# GameboyCartridgeKS.net
KiCad netlist of a schematic drawn in EAGLE
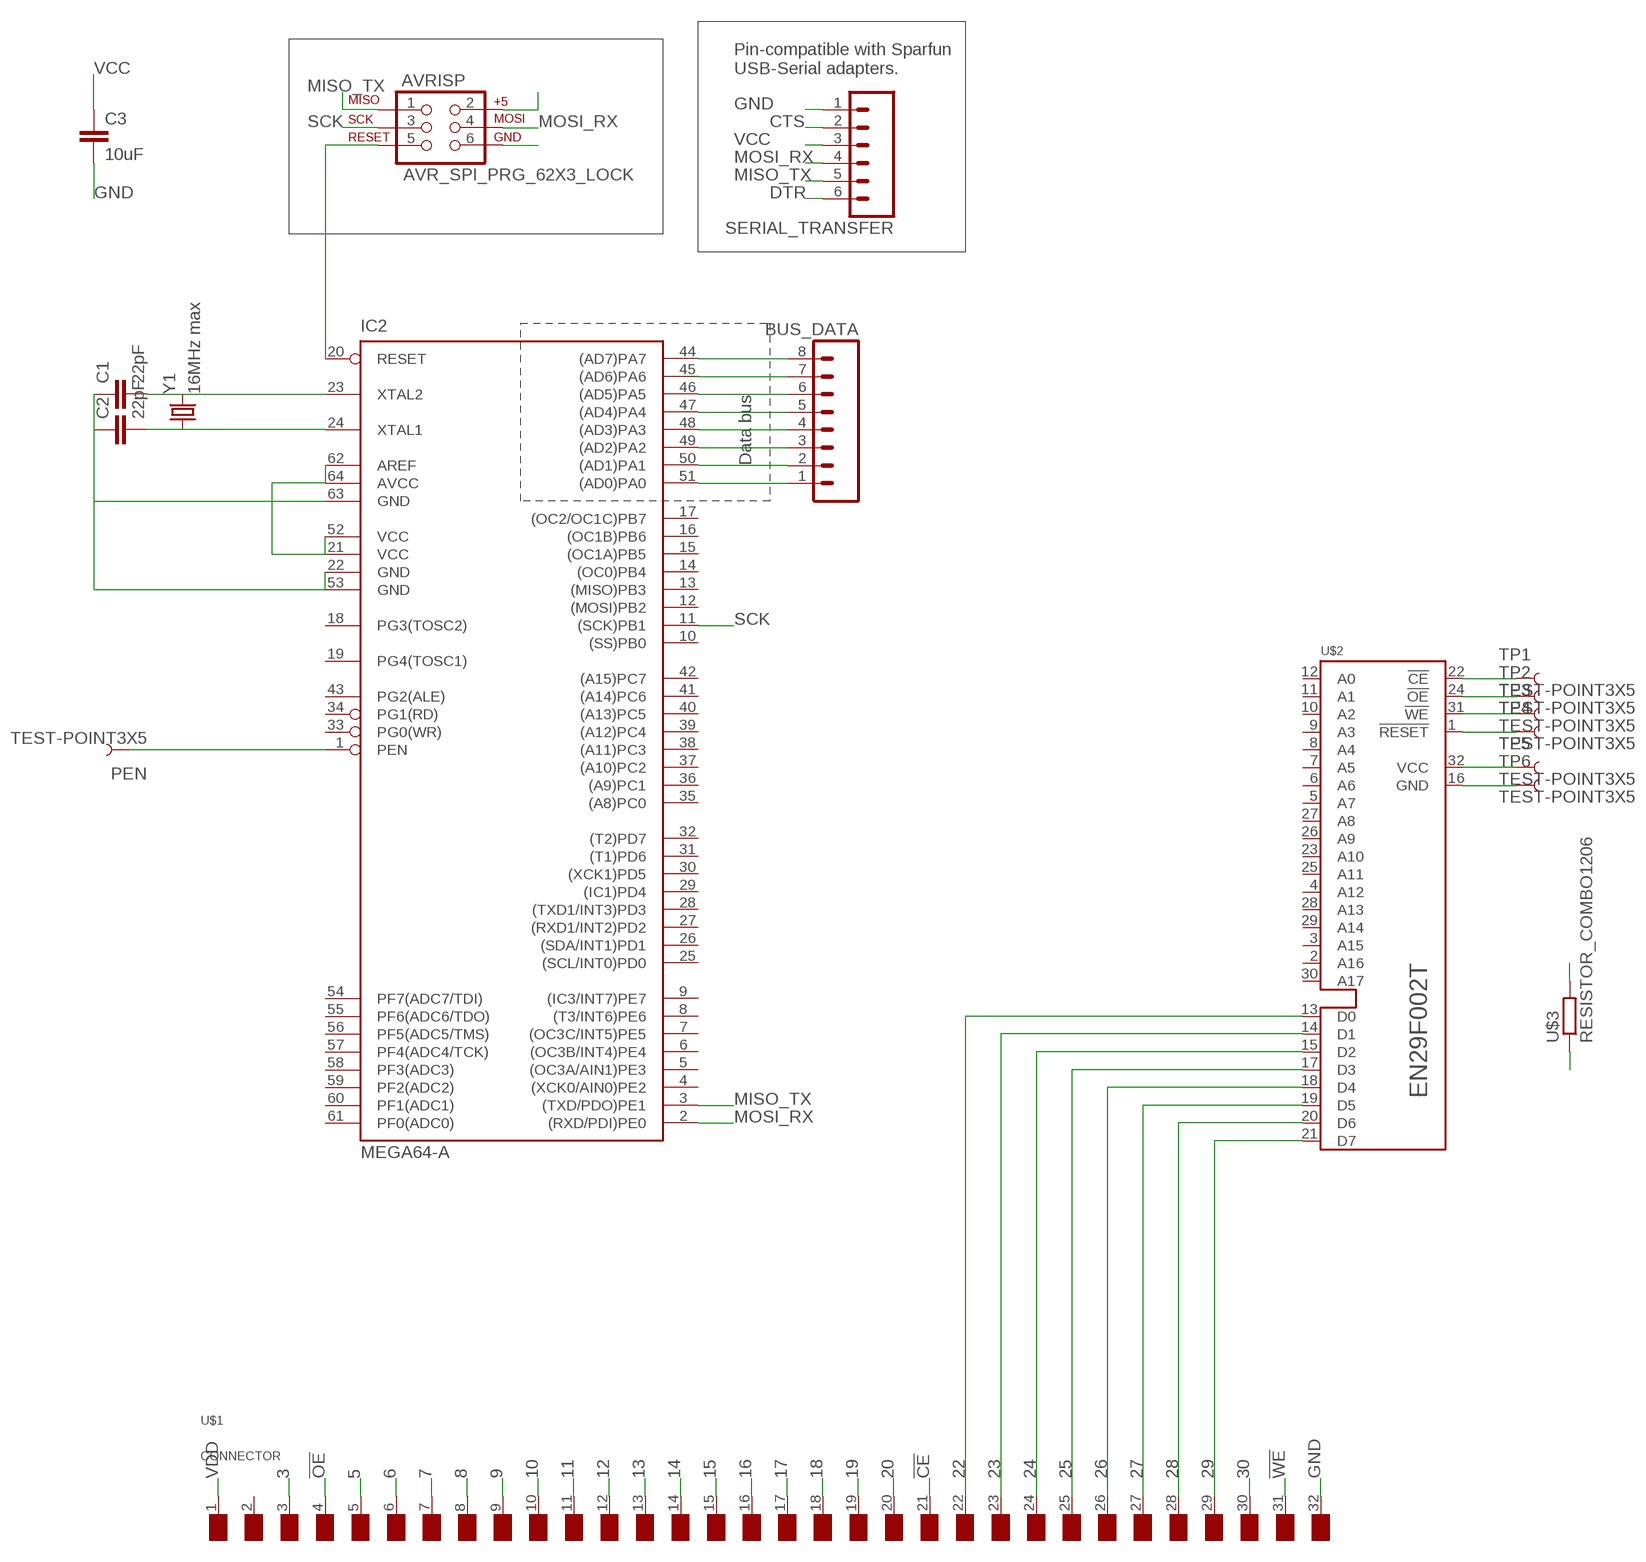
[diagram p0: schematic, sheet 1]

(export (version "E")
  (design (tool "Eeschema 10.0.6"))
  (components
    (comp (ref "AVRISP")
      (value "AVR_SPI_PRG_62X3_LOCK")
      (footprint "eagle-import:2X3_LOCK")
      (libsource (lib "eagle-import") (part "AVR_SPI_PRG_62X3_LOCK"))
    )
    (comp (ref "BUS_DATA")
      (value "M08NO_SILK")
      (footprint "eagle-import:1X08_PIN1_NO_SILK")
      (libsource (lib "eagle-import") (part "M08NO_SILK"))
    )
    (comp (ref "C1")
      (value "22pF")
      (footprint "eagle-import:C0805K")
      (libsource (lib "eagle-import") (part "C-EUC0805K"))
    )
    (comp (ref "C2")
      (value "22pF")
      (footprint "eagle-import:C0805K")
      (libsource (lib "eagle-import") (part "C-EUC0805K"))
    )
    (comp (ref "C3")
      (value "10uF")
      (footprint "eagle-import:C1206K")
      (libsource (lib "eagle-import") (part "C-EUC1206K"))
    )
    (comp (ref "IC2")
      (value "MEGA64-A")
      (footprint "eagle-import:TQFP64")
      (fields (field (name "MPN") "ATMEGA64-16AU"))
      (libsource (lib "eagle-import") (part "MEGA64-A"))
    )
    (comp (ref "PEN")
      (value "TEST-POINT3X5")
      (footprint "eagle-import:PAD.03X.05")
      (libsource (lib "eagle-import") (part "TEST-POINT3X5"))
    )
    (comp (ref "SERIAL_TRANSFER")
      (value "M06SILK_FEMALE_PTH")
      (footprint "eagle-import:1X06")
      (libsource (lib "eagle-import") (part "M06SILK_FEMALE_PTH"))
    )
    (comp (ref "TP1")
      (value "TEST-POINT3X5")
      (footprint "eagle-import:PAD.03X.05")
      (libsource (lib "eagle-import") (part "TEST-POINT3X5"))
    )
    (comp (ref "TP2")
      (value "TEST-POINT3X5")
      (footprint "eagle-import:PAD.03X.05")
      (libsource (lib "eagle-import") (part "TEST-POINT3X5"))
    )
    (comp (ref "TP3")
      (value "TEST-POINT3X5")
      (footprint "eagle-import:PAD.03X.05")
      (libsource (lib "eagle-import") (part "TEST-POINT3X5"))
    )
    (comp (ref "TP4")
      (value "TEST-POINT3X5")
      (footprint "eagle-import:PAD.03X.05")
      (libsource (lib "eagle-import") (part "TEST-POINT3X5"))
    )
    (comp (ref "TP5")
      (value "TEST-POINT3X5")
      (footprint "eagle-import:PAD.03X.05")
      (libsource (lib "eagle-import") (part "TEST-POINT3X5"))
    )
    (comp (ref "TP6")
      (value "TEST-POINT3X5")
      (footprint "eagle-import:PAD.03X.05")
      (libsource (lib "eagle-import") (part "TEST-POINT3X5"))
    )
    (comp (ref "U$1")
      (value "CONNECTOR")
      (footprint "eagle-import:CONNECTOR")
      (libsource (lib "eagle-import") (part "CONNECTOR"))
    )
    (comp (ref "U$2")
      (value "EN29F002T")
      (footprint "eagle-import:PLCC-S32")
      (libsource (lib "eagle-import") (part "EN29F002T"))
    )
    (comp (ref "U$3")
      (value "RESISTOR_COMBO1206")
      (footprint "eagle-import:207-10_SMD_COMBO")
      (libsource (lib "eagle-import") (part "RESISTOR_COMBO1206"))
    )
    (comp (ref "Y1")
      (value "16MHz max")
      (footprint "eagle-import:HC49U-V")
      (libsource (lib "eagle-import") (part "CRYSTALHC49UV"))
    )
  )
  (nets
    (net (code "1") (name "/3") (class "Default")
      (node (ref "U$1") (pin "3") (pinfunction "/WR_3") (pintype "bidirectional"))
    )
    (net (code "2") (name "/5") (class "Default")
      (node (ref "U$1") (pin "5") (pinfunction "/RCS_5") (pintype "bidirectional"))
    )
    (net (code "3") (name "/6") (class "Default")
      (node (ref "U$1") (pin "6") (pinfunction "A0_6") (pintype "bidirectional"))
    )
    (net (code "4") (name "/7") (class "Default")
      (node (ref "U$1") (pin "7") (pinfunction "A1_7") (pintype "bidirectional"))
    )
    (net (code "5") (name "/8") (class "Default")
      (node (ref "U$1") (pin "8") (pinfunction "A2_8") (pintype "bidirectional"))
    )
    (net (code "6") (name "/9") (class "Default")
      (node (ref "U$1") (pin "9") (pinfunction "A3_9") (pintype "bidirectional"))
    )
    (net (code "7") (name "/10") (class "Default")
      (node (ref "U$1") (pin "10") (pinfunction "A4_10") (pintype "bidirectional"))
    )
    (net (code "8") (name "/11") (class "Default")
      (node (ref "U$1") (pin "11") (pinfunction "A5_11") (pintype "bidirectional"))
    )
    (net (code "9") (name "/12") (class "Default")
      (node (ref "U$1") (pin "12") (pinfunction "A6_12") (pintype "bidirectional"))
    )
    (net (code "10") (name "/13") (class "Default")
      (node (ref "U$1") (pin "13") (pinfunction "A7_13") (pintype "bidirectional"))
    )
    (net (code "11") (name "/14") (class "Default")
      (node (ref "U$1") (pin "14") (pinfunction "A8_14") (pintype "bidirectional"))
    )
    (net (code "12") (name "/15") (class "Default")
      (node (ref "U$1") (pin "15") (pinfunction "A9_15") (pintype "bidirectional"))
    )
    (net (code "13") (name "/16") (class "Default")
      (node (ref "U$1") (pin "16") (pinfunction "A10_16") (pintype "bidirectional"))
    )
    (net (code "14") (name "/17") (class "Default")
      (node (ref "U$1") (pin "17") (pinfunction "A11_17") (pintype "bidirectional"))
    )
    (net (code "15") (name "/18") (class "Default")
      (node (ref "U$1") (pin "18") (pinfunction "A12_18") (pintype "bidirectional"))
    )
    (net (code "16") (name "/19") (class "Default")
      (node (ref "U$1") (pin "19") (pinfunction "A13_19") (pintype "bidirectional"))
    )
    (net (code "17") (name "/20") (class "Default")
      (node (ref "U$1") (pin "20") (pinfunction "A14_20") (pintype "bidirectional"))
    )
    (net (code "18") (name "/22") (class "Default")
      (node (ref "BUS_DATA") (pin "1") (pinfunction "1_1") (pintype "passive"))
      (node (ref "IC2") (pin "51") (pinfunction "(AD0)PA0_51") (pintype "bidirectional"))
      (node (ref "U$1") (pin "22") (pinfunction "D0_22") (pintype "bidirectional"))
      (node (ref "U$2") (pin "13") (pinfunction "D0_13") (pintype "bidirectional"))
    )
    (net (code "19") (name "/23") (class "Default")
      (node (ref "BUS_DATA") (pin "2") (pinfunction "2_2") (pintype "passive"))
      (node (ref "IC2") (pin "50") (pinfunction "(AD1)PA1_50") (pintype "bidirectional"))
      (node (ref "U$1") (pin "23") (pinfunction "D1_23") (pintype "bidirectional"))
      (node (ref "U$2") (pin "14") (pinfunction "D1_14") (pintype "bidirectional"))
    )
    (net (code "20") (name "/24") (class "Default")
      (node (ref "BUS_DATA") (pin "3") (pinfunction "3_3") (pintype "passive"))
      (node (ref "IC2") (pin "49") (pinfunction "(AD2)PA2_49") (pintype "bidirectional"))
      (node (ref "U$1") (pin "24") (pinfunction "D2_24") (pintype "bidirectional"))
      (node (ref "U$2") (pin "15") (pinfunction "D2_15") (pintype "bidirectional"))
    )
    (net (code "21") (name "/25") (class "Default")
      (node (ref "BUS_DATA") (pin "4") (pinfunction "4_4") (pintype "passive"))
      (node (ref "IC2") (pin "48") (pinfunction "(AD3)PA3_48") (pintype "bidirectional"))
      (node (ref "U$1") (pin "25") (pinfunction "D3_25") (pintype "bidirectional"))
      (node (ref "U$2") (pin "17") (pinfunction "D3_17") (pintype "bidirectional"))
    )
    (net (code "22") (name "/26") (class "Default")
      (node (ref "BUS_DATA") (pin "5") (pinfunction "5_5") (pintype "passive"))
      (node (ref "IC2") (pin "47") (pinfunction "(AD4)PA4_47") (pintype "bidirectional"))
      (node (ref "U$1") (pin "26") (pinfunction "D4_26") (pintype "bidirectional"))
      (node (ref "U$2") (pin "18") (pinfunction "D4_18") (pintype "bidirectional"))
    )
    (net (code "23") (name "/27") (class "Default")
      (node (ref "BUS_DATA") (pin "6") (pinfunction "6_6") (pintype "passive"))
      (node (ref "IC2") (pin "46") (pinfunction "(AD5)PA5_46") (pintype "bidirectional"))
      (node (ref "U$1") (pin "27") (pinfunction "D5_27") (pintype "bidirectional"))
      (node (ref "U$2") (pin "19") (pinfunction "D5_19") (pintype "bidirectional"))
    )
    (net (code "24") (name "/28") (class "Default")
      (node (ref "BUS_DATA") (pin "7") (pinfunction "7_7") (pintype "passive"))
      (node (ref "IC2") (pin "45") (pinfunction "(AD6)PA6_45") (pintype "bidirectional"))
      (node (ref "U$1") (pin "28") (pinfunction "D6_28") (pintype "bidirectional"))
      (node (ref "U$2") (pin "20") (pinfunction "D6_20") (pintype "bidirectional"))
    )
    (net (code "25") (name "/29") (class "Default")
      (node (ref "BUS_DATA") (pin "8") (pinfunction "8_8") (pintype "passive"))
      (node (ref "IC2") (pin "44") (pinfunction "(AD7)PA7_44") (pintype "bidirectional"))
      (node (ref "U$1") (pin "29") (pinfunction "D7_29") (pintype "bidirectional"))
      (node (ref "U$2") (pin "21") (pinfunction "D7_21") (pintype "bidirectional"))
    )
    (net (code "26") (name "/30") (class "Default")
      (node (ref "U$1") (pin "30") (pinfunction "/RS_30") (pintype "bidirectional"))
    )
    (net (code "27") (name "/CTS") (class "Default")
      (node (ref "SERIAL_TRANSFER") (pin "2") (pinfunction "2_2") (pintype "passive"))
    )
    (net (code "28") (name "/DTR") (class "Default")
      (node (ref "SERIAL_TRANSFER") (pin "6") (pinfunction "6_6") (pintype "passive"))
    )
    (net (code "29") (name "/GND") (class "Default")
      (node (ref "AVRISP") (pin "6") (pinfunction "6_6") (pintype "passive"))
      (node (ref "C1") (pin "1") (pinfunction "1_1") (pintype "passive"))
      (node (ref "C2") (pin "1") (pinfunction "1_1") (pintype "passive"))
      (node (ref "C3") (pin "2") (pinfunction "2_2") (pintype "passive"))
      (node (ref "IC2") (pin "22") (pinfunction "GND_22") (pintype "power_in"))
      (node (ref "IC2") (pin "53") (pinfunction "GND_53") (pintype "power_in"))
      (node (ref "IC2") (pin "63") (pinfunction "GND_63") (pintype "power_in"))
      (node (ref "SERIAL_TRANSFER") (pin "1") (pinfunction "1_1") (pintype "passive"))
      (node (ref "TP6") (pin "P$1") (pinfunction "1_P$1") (pintype "bidirectional"))
      (node (ref "U$1") (pin "32") (pinfunction "GND_32") (pintype "power_in"))
      (node (ref "U$2") (pin "16") (pinfunction "GND_16") (pintype "input"))
    )
    (net (code "30") (name "/MISO_TX") (class "Default")
      (node (ref "AVRISP") (pin "1") (pinfunction "1_1") (pintype "passive"))
      (node (ref "IC2") (pin "3") (pinfunction "(TXD/PDO)PE1_3") (pintype "bidirectional"))
      (node (ref "SERIAL_TRANSFER") (pin "5") (pinfunction "5_5") (pintype "passive"))
    )
    (net (code "31") (name "/MOSI_RX") (class "Default")
      (node (ref "AVRISP") (pin "4") (pinfunction "4_4") (pintype "passive"))
      (node (ref "IC2") (pin "2") (pinfunction "(RXD/PDI)PE0_2") (pintype "bidirectional"))
      (node (ref "SERIAL_TRANSFER") (pin "4") (pinfunction "4_4") (pintype "passive"))
    )
    (net (code "32") (name "/SCK") (class "Default")
      (node (ref "AVRISP") (pin "3") (pinfunction "3_3") (pintype "passive"))
      (node (ref "IC2") (pin "11") (pinfunction "(SCK)PB1_11") (pintype "bidirectional"))
    )
    (net (code "33") (name "/VCC") (class "Default")
      (node (ref "AVRISP") (pin "2") (pinfunction "2_2") (pintype "passive"))
      (node (ref "C3") (pin "1") (pinfunction "1_1") (pintype "passive"))
      (node (ref "IC2") (pin "21") (pinfunction "VCC_21") (pintype "power_in"))
      (node (ref "IC2") (pin "52") (pinfunction "VCC_52") (pintype "power_in"))
      (node (ref "IC2") (pin "62") (pinfunction "AREF_62") (pintype "passive"))
      (node (ref "IC2") (pin "64") (pinfunction "AVCC_64") (pintype "power_in"))
      (node (ref "SERIAL_TRANSFER") (pin "3") (pinfunction "3_3") (pintype "passive"))
      (node (ref "TP5") (pin "P$1") (pinfunction "1_P$1") (pintype "bidirectional"))
      (node (ref "U$2") (pin "32") (pinfunction "VCC_32") (pintype "input"))
      (node (ref "U$3") (pin "2") (pinfunction "2_2") (pintype "passive"))
      (node (ref "U$3") (pin "3") (pinfunction "2_3") (pintype "passive"))
    )
    (net (code "34") (name "/VDD") (class "Default")
      (node (ref "U$1") (pin "1") (pinfunction "VDD_1") (pintype "power_in"))
    )
    (net (code "35") (name "/~{CE}") (class "Default")
      (node (ref "TP1") (pin "P$1") (pinfunction "1_P$1") (pintype "bidirectional"))
      (node (ref "U$1") (pin "21") (pinfunction "A15_21") (pintype "bidirectional"))
      (node (ref "U$2") (pin "22") (pinfunction "~{CE}_22") (pintype "input"))
    )
    (net (code "36") (name "/~{OE}") (class "Default")
      (node (ref "TP2") (pin "P$1") (pinfunction "1_P$1") (pintype "bidirectional"))
      (node (ref "U$1") (pin "4") (pinfunction "/RD_4") (pintype "bidirectional"))
      (node (ref "U$2") (pin "24") (pinfunction "~{OE}_24") (pintype "input"))
    )
    (net (code "37") (name "/~{WE}") (class "Default")
      (node (ref "TP3") (pin "P$1") (pinfunction "1_P$1") (pintype "bidirectional"))
      (node (ref "U$1") (pin "31") (pinfunction "VIN_31") (pintype "bidirectional"))
      (node (ref "U$2") (pin "31") (pinfunction "~{WE}_31") (pintype "input"))
      (node (ref "U$3") (pin "1") (pinfunction "1_1") (pintype "passive"))
      (node (ref "U$3") (pin "4") (pinfunction "1_4") (pintype "passive"))
    )
    (net (code "38") (name "Net-(IC2-PEN)") (class "Default")
      (node (ref "IC2") (pin "1") (pinfunction "PEN_1") (pintype "input"))
      (node (ref "PEN") (pin "P$1") (pinfunction "1_P$1") (pintype "bidirectional"))
    )
    (net (code "39") (name "Net-(IC2-RESET)") (class "Default")
      (node (ref "AVRISP") (pin "5") (pinfunction "5_5") (pintype "passive"))
      (node (ref "IC2") (pin "20") (pinfunction "RESET_20") (pintype "input"))
    )
    (net (code "40") (name "Net-(IC2-XTAL1)") (class "Default")
      (node (ref "C2") (pin "2") (pinfunction "2_2") (pintype "passive"))
      (node (ref "IC2") (pin "24") (pinfunction "XTAL1_24") (pintype "bidirectional"))
      (node (ref "Y1") (pin "1") (pinfunction "1_1") (pintype "passive"))
    )
    (net (code "41") (name "Net-(IC2-XTAL2)") (class "Default")
      (node (ref "C1") (pin "2") (pinfunction "2_2") (pintype "passive"))
      (node (ref "IC2") (pin "23") (pinfunction "XTAL2_23") (pintype "bidirectional"))
      (node (ref "Y1") (pin "2") (pinfunction "2_2") (pintype "passive"))
    )
    (net (code "42") (name "Net-(TP4-1)") (class "Default")
      (node (ref "TP4") (pin "P$1") (pinfunction "1_P$1") (pintype "bidirectional"))
      (node (ref "U$2") (pin "1") (pinfunction "~{RESET}_1") (pintype "input"))
    )
    (net (code "43") (name "unconnected-(IC2-(A8)PC0-Pad35)") (class "Default")
      (node (ref "IC2") (pin "35") (pinfunction "(A8)PC0_35") (pintype "output"))
    )
    (net (code "44") (name "unconnected-(IC2-(A9)PC1-Pad36)") (class "Default")
      (node (ref "IC2") (pin "36") (pinfunction "(A9)PC1_36") (pintype "output"))
    )
    (net (code "45") (name "unconnected-(IC2-(A10)PC2-Pad37)") (class "Default")
      (node (ref "IC2") (pin "37") (pinfunction "(A10)PC2_37") (pintype "output"))
    )
    (net (code "46") (name "unconnected-(IC2-(A11)PC3-Pad38)") (class "Default")
      (node (ref "IC2") (pin "38") (pinfunction "(A11)PC3_38") (pintype "output"))
    )
    (net (code "47") (name "unconnected-(IC2-(A12)PC4-Pad39)") (class "Default")
      (node (ref "IC2") (pin "39") (pinfunction "(A12)PC4_39") (pintype "output"))
    )
    (net (code "48") (name "unconnected-(IC2-(A13)PC5-Pad40)") (class "Default")
      (node (ref "IC2") (pin "40") (pinfunction "(A13)PC5_40") (pintype "output"))
    )
    (net (code "49") (name "unconnected-(IC2-(A14)PC6-Pad41)") (class "Default")
      (node (ref "IC2") (pin "41") (pinfunction "(A14)PC6_41") (pintype "output"))
    )
    (net (code "50") (name "unconnected-(IC2-(A15)PC7-Pad42)") (class "Default")
      (node (ref "IC2") (pin "42") (pinfunction "(A15)PC7_42") (pintype "output"))
    )
    (net (code "51") (name "unconnected-(IC2-(IC1)PD4-Pad29)") (class "Default")
      (node (ref "IC2") (pin "29") (pinfunction "(IC1)PD4_29") (pintype "bidirectional"))
    )
    (net (code "52") (name "unconnected-(IC2-(IC3{slash}INT7)PE7-Pad9)") (class "Default")
      (node (ref "IC2") (pin "9") (pinfunction "(IC3/INT7)PE7_9") (pintype "bidirectional"))
    )
    (net (code "53") (name "unconnected-(IC2-(MISO)PB3-Pad13)") (class "Default")
      (node (ref "IC2") (pin "13") (pinfunction "(MISO)PB3_13") (pintype "bidirectional"))
    )
    (net (code "54") (name "unconnected-(IC2-(MOSI)PB2-Pad12)") (class "Default")
      (node (ref "IC2") (pin "12") (pinfunction "(MOSI)PB2_12") (pintype "bidirectional"))
    )
    (net (code "55") (name "unconnected-(IC2-(OC0)PB4-Pad14)") (class "Default")
      (node (ref "IC2") (pin "14") (pinfunction "(OC0)PB4_14") (pintype "bidirectional"))
    )
    (net (code "56") (name "unconnected-(IC2-(OC1A)PB5-Pad15)") (class "Default")
      (node (ref "IC2") (pin "15") (pinfunction "(OC1A)PB5_15") (pintype "bidirectional"))
    )
    (net (code "57") (name "unconnected-(IC2-(OC1B)PB6-Pad16)") (class "Default")
      (node (ref "IC2") (pin "16") (pinfunction "(OC1B)PB6_16") (pintype "bidirectional"))
    )
    (net (code "58") (name "unconnected-(IC2-(OC2{slash}OC1C)PB7-Pad17)") (class "Default")
      (node (ref "IC2") (pin "17") (pinfunction "(OC2/OC1C)PB7_17") (pintype "bidirectional"))
    )
    (net (code "59") (name "unconnected-(IC2-(OC3A{slash}AIN1)PE3-Pad5)") (class "Default")
      (node (ref "IC2") (pin "5") (pinfunction "(OC3A/AIN1)PE3_5") (pintype "bidirectional"))
    )
    (net (code "60") (name "unconnected-(IC2-(OC3B{slash}INT4)PE4-Pad6)") (class "Default")
      (node (ref "IC2") (pin "6") (pinfunction "(OC3B/INT4)PE4_6") (pintype "bidirectional"))
    )
    (net (code "61") (name "unconnected-(IC2-(OC3C{slash}INT5)PE5-Pad7)") (class "Default")
      (node (ref "IC2") (pin "7") (pinfunction "(OC3C/INT5)PE5_7") (pintype "bidirectional"))
    )
    (net (code "62") (name "unconnected-(IC2-(RXD1{slash}INT2)PD2-Pad27)") (class "Default")
      (node (ref "IC2") (pin "27") (pinfunction "(RXD1/INT2)PD2_27") (pintype "bidirectional"))
    )
    (net (code "63") (name "unconnected-(IC2-(SCL{slash}INT0)PD0-Pad25)") (class "Default")
      (node (ref "IC2") (pin "25") (pinfunction "(SCL/INT0)PD0_25") (pintype "bidirectional"))
    )
    (net (code "64") (name "unconnected-(IC2-(SDA{slash}INT1)PD1-Pad26)") (class "Default")
      (node (ref "IC2") (pin "26") (pinfunction "(SDA/INT1)PD1_26") (pintype "bidirectional"))
    )
    (net (code "65") (name "unconnected-(IC2-(SS)PB0-Pad10)") (class "Default")
      (node (ref "IC2") (pin "10") (pinfunction "(SS)PB0_10") (pintype "bidirectional"))
    )
    (net (code "66") (name "unconnected-(IC2-(T1)PD6-Pad31)") (class "Default")
      (node (ref "IC2") (pin "31") (pinfunction "(T1)PD6_31") (pintype "bidirectional"))
    )
    (net (code "67") (name "unconnected-(IC2-(T2)PD7-Pad32)") (class "Default")
      (node (ref "IC2") (pin "32") (pinfunction "(T2)PD7_32") (pintype "bidirectional"))
    )
    (net (code "68") (name "unconnected-(IC2-(T3{slash}INT6)PE6-Pad8)") (class "Default")
      (node (ref "IC2") (pin "8") (pinfunction "(T3/INT6)PE6_8") (pintype "bidirectional"))
    )
    (net (code "69") (name "unconnected-(IC2-(TXD1{slash}INT3)PD3-Pad28)") (class "Default")
      (node (ref "IC2") (pin "28") (pinfunction "(TXD1/INT3)PD3_28") (pintype "bidirectional"))
    )
    (net (code "70") (name "unconnected-(IC2-(XCK0{slash}AIN0)PE2-Pad4)") (class "Default")
      (node (ref "IC2") (pin "4") (pinfunction "(XCK0/AIN0)PE2_4") (pintype "bidirectional"))
    )
    (net (code "71") (name "unconnected-(IC2-(XCK1)PD5-Pad30)") (class "Default")
      (node (ref "IC2") (pin "30") (pinfunction "(XCK1)PD5_30") (pintype "bidirectional"))
    )
    (net (code "72") (name "unconnected-(IC2-PF0(ADC0)-Pad61)") (class "Default")
      (node (ref "IC2") (pin "61") (pinfunction "PF0(ADC0)_61") (pintype "input"))
    )
    (net (code "73") (name "unconnected-(IC2-PF1(ADC1)-Pad60)") (class "Default")
      (node (ref "IC2") (pin "60") (pinfunction "PF1(ADC1)_60") (pintype "input"))
    )
    (net (code "74") (name "unconnected-(IC2-PF2(ADC2)-Pad59)") (class "Default")
      (node (ref "IC2") (pin "59") (pinfunction "PF2(ADC2)_59") (pintype "input"))
    )
    (net (code "75") (name "unconnected-(IC2-PF3(ADC3)-Pad58)") (class "Default")
      (node (ref "IC2") (pin "58") (pinfunction "PF3(ADC3)_58") (pintype "input"))
    )
    (net (code "76") (name "unconnected-(IC2-PF4(ADC4{slash}TCK)-Pad57)") (class "Default")
      (node (ref "IC2") (pin "57") (pinfunction "PF4(ADC4/TCK)_57") (pintype "input"))
    )
    (net (code "77") (name "unconnected-(IC2-PF5(ADC5{slash}TMS)-Pad56)") (class "Default")
      (node (ref "IC2") (pin "56") (pinfunction "PF5(ADC5/TMS)_56") (pintype "input"))
    )
    (net (code "78") (name "unconnected-(IC2-PF6(ADC6{slash}TDO)-Pad55)") (class "Default")
      (node (ref "IC2") (pin "55") (pinfunction "PF6(ADC6/TDO)_55") (pintype "input"))
    )
    (net (code "79") (name "unconnected-(IC2-PF7(ADC7{slash}TDI)-Pad54)") (class "Default")
      (node (ref "IC2") (pin "54") (pinfunction "PF7(ADC7/TDI)_54") (pintype "input"))
    )
    (net (code "80") (name "unconnected-(IC2-PG0(WR)-Pad33)") (class "Default")
      (node (ref "IC2") (pin "33") (pinfunction "PG0(WR)_33") (pintype "bidirectional"))
    )
    (net (code "81") (name "unconnected-(IC2-PG1(RD)-Pad34)") (class "Default")
      (node (ref "IC2") (pin "34") (pinfunction "PG1(RD)_34") (pintype "bidirectional"))
    )
    (net (code "82") (name "unconnected-(IC2-PG2(ALE)-Pad43)") (class "Default")
      (node (ref "IC2") (pin "43") (pinfunction "PG2(ALE)_43") (pintype "bidirectional"))
    )
    (net (code "83") (name "unconnected-(IC2-PG3(TOSC2)-Pad18)") (class "Default")
      (node (ref "IC2") (pin "18") (pinfunction "PG3(TOSC2)_18") (pintype "bidirectional"))
    )
    (net (code "84") (name "unconnected-(IC2-PG4(TOSC1)-Pad19)") (class "Default")
      (node (ref "IC2") (pin "19") (pinfunction "PG4(TOSC1)_19") (pintype "bidirectional"))
    )
    (net (code "85") (name "unconnected-(U$1-NC-Pad2)") (class "Default")
      (node (ref "U$1") (pin "2") (pinfunction "NC_2") (pintype "no_connect"))
    )
    (net (code "86") (name "unconnected-(U$2-A0-Pad12)") (class "Default")
      (node (ref "U$2") (pin "12") (pinfunction "A0_12") (pintype "input"))
    )
    (net (code "87") (name "unconnected-(U$2-A1-Pad11)") (class "Default")
      (node (ref "U$2") (pin "11") (pinfunction "A1_11") (pintype "input"))
    )
    (net (code "88") (name "unconnected-(U$2-A2-Pad10)") (class "Default")
      (node (ref "U$2") (pin "10") (pinfunction "A2_10") (pintype "input"))
    )
    (net (code "89") (name "unconnected-(U$2-A3-Pad9)") (class "Default")
      (node (ref "U$2") (pin "9") (pinfunction "A3_9") (pintype "input"))
    )
    (net (code "90") (name "unconnected-(U$2-A4-Pad8)") (class "Default")
      (node (ref "U$2") (pin "8") (pinfunction "A4_8") (pintype "input"))
    )
    (net (code "91") (name "unconnected-(U$2-A5-Pad7)") (class "Default")
      (node (ref "U$2") (pin "7") (pinfunction "A5_7") (pintype "input"))
    )
    (net (code "92") (name "unconnected-(U$2-A6-Pad6)") (class "Default")
      (node (ref "U$2") (pin "6") (pinfunction "A6_6") (pintype "input"))
    )
    (net (code "93") (name "unconnected-(U$2-A7-Pad5)") (class "Default")
      (node (ref "U$2") (pin "5") (pinfunction "A7_5") (pintype "input"))
    )
    (net (code "94") (name "unconnected-(U$2-A8-Pad27)") (class "Default")
      (node (ref "U$2") (pin "27") (pinfunction "A8_27") (pintype "input"))
    )
    (net (code "95") (name "unconnected-(U$2-A9-Pad26)") (class "Default")
      (node (ref "U$2") (pin "26") (pinfunction "A9_26") (pintype "input"))
    )
    (net (code "96") (name "unconnected-(U$2-A10-Pad23)") (class "Default")
      (node (ref "U$2") (pin "23") (pinfunction "A10_23") (pintype "input"))
    )
    (net (code "97") (name "unconnected-(U$2-A11-Pad25)") (class "Default")
      (node (ref "U$2") (pin "25") (pinfunction "A11_25") (pintype "input"))
    )
    (net (code "98") (name "unconnected-(U$2-A12-Pad4)") (class "Default")
      (node (ref "U$2") (pin "4") (pinfunction "A12_4") (pintype "input"))
    )
    (net (code "99") (name "unconnected-(U$2-A13-Pad28)") (class "Default")
      (node (ref "U$2") (pin "28") (pinfunction "A13_28") (pintype "input"))
    )
    (net (code "100") (name "unconnected-(U$2-A14-Pad29)") (class "Default")
      (node (ref "U$2") (pin "29") (pinfunction "A14_29") (pintype "input"))
    )
    (net (code "101") (name "unconnected-(U$2-A15-Pad3)") (class "Default")
      (node (ref "U$2") (pin "3") (pinfunction "A15_3") (pintype "input"))
    )
    (net (code "102") (name "unconnected-(U$2-A16-Pad2)") (class "Default")
      (node (ref "U$2") (pin "2") (pinfunction "A16_2") (pintype "input"))
    )
    (net (code "103") (name "unconnected-(U$2-A17-Pad30)") (class "Default")
      (node (ref "U$2") (pin "30") (pinfunction "A17_30") (pintype "input"))
    )
  )
)
